# 3_way_omnetics_small.net
KiCad netlist of a schematic drawn in EAGLE
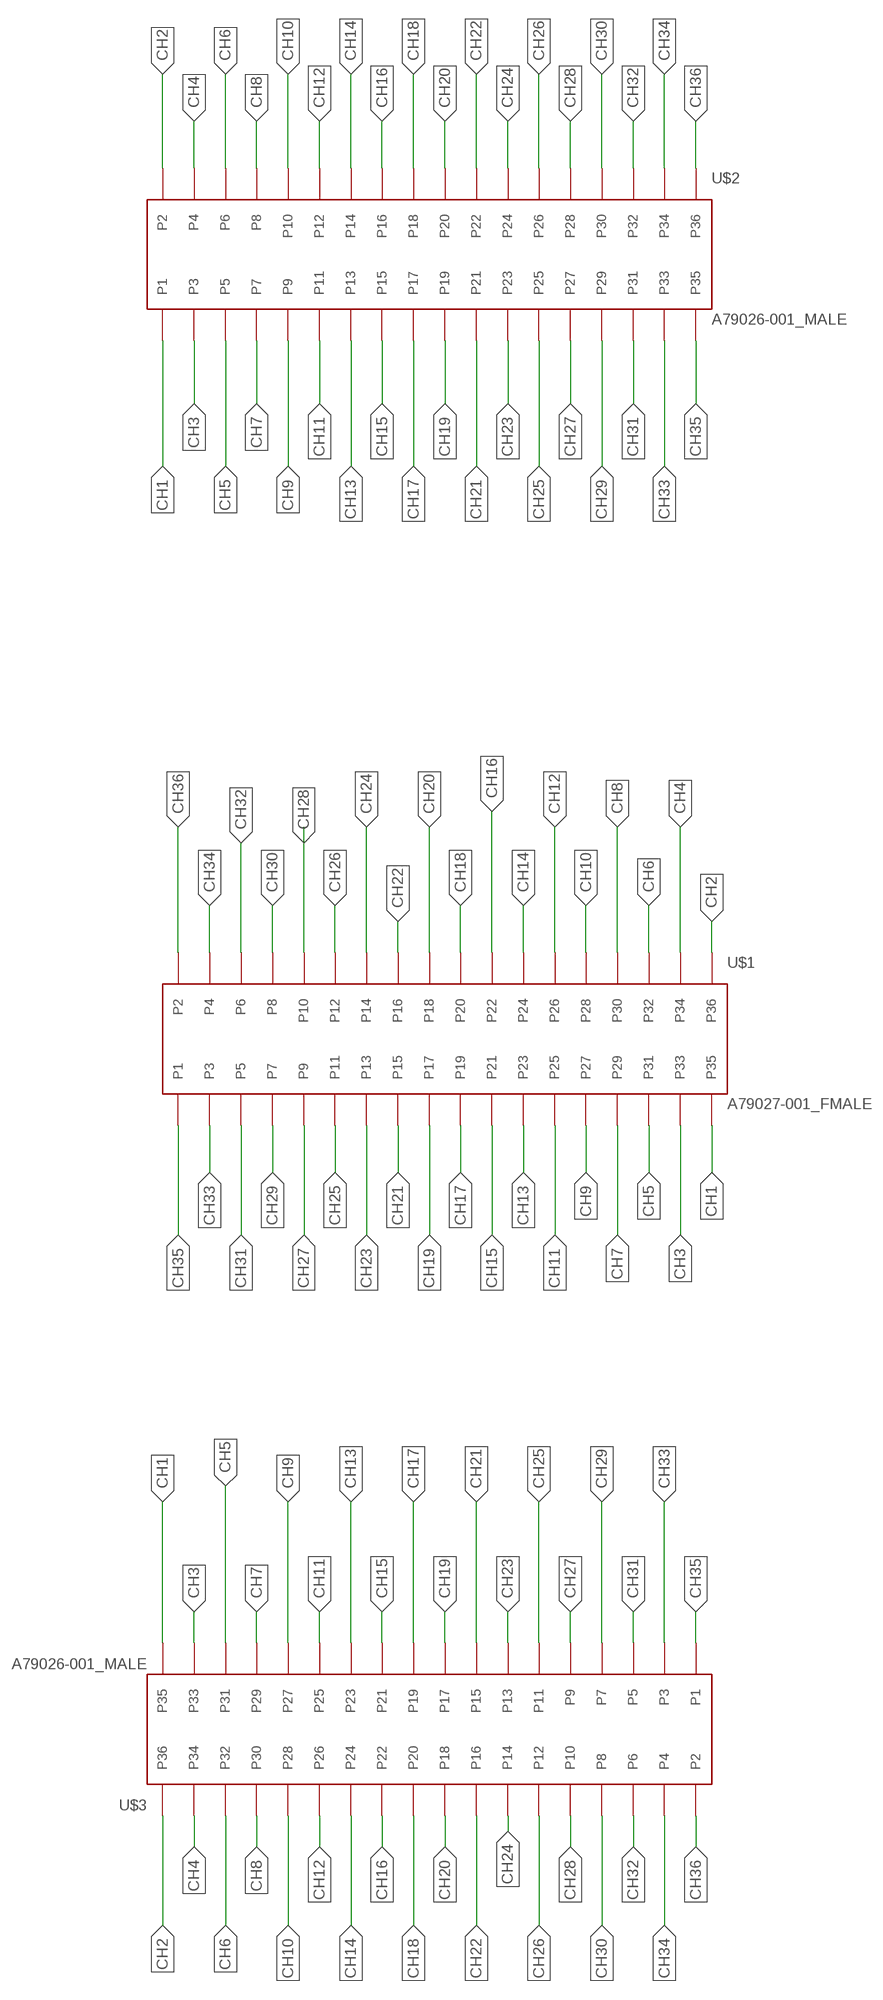
[diagram p0: schematic, sheet 1]

(export (version "E")
  (design (tool "Eeschema 10.0.6"))
  (components
    (comp (ref "U$1")
      (value "A79027-001_FMALE")
      (footprint "eagle-import:A79026-001_MALE")
      (libsource (lib "eagle-import") (part "A79027-001_FMALE"))
    )
    (comp (ref "U$2")
      (value "A79026-001_MALE")
      (footprint "eagle-import:A79026-001_MALE")
      (libsource (lib "eagle-import") (part "A79026-001_MALE"))
    )
    (comp (ref "U$3")
      (value "A79026-001_MALE")
      (footprint "eagle-import:A79026-001_MALE")
      (libsource (lib "eagle-import") (part "A79026-001_MALE"))
    )
  )
  (nets
    (net (code "1") (name "CH1") (class "Default")
      (node (ref "U$1") (pin "P35") (pinfunction "P35_P35") (pintype "bidirectional"))
      (node (ref "U$2") (pin "P1") (pinfunction "P1_P1") (pintype "bidirectional"))
      (node (ref "U$3") (pin "P35") (pinfunction "P35_P35") (pintype "bidirectional"))
    )
    (net (code "2") (name "CH2") (class "Default")
      (node (ref "U$1") (pin "P36") (pinfunction "P36_P36") (pintype "bidirectional"))
      (node (ref "U$2") (pin "P2") (pinfunction "P2_P2") (pintype "bidirectional"))
      (node (ref "U$3") (pin "P36") (pinfunction "P36_P36") (pintype "bidirectional"))
    )
    (net (code "3") (name "CH3") (class "Default")
      (node (ref "U$1") (pin "P33") (pinfunction "P33_P33") (pintype "bidirectional"))
      (node (ref "U$2") (pin "P3") (pinfunction "P3_P3") (pintype "bidirectional"))
      (node (ref "U$3") (pin "P33") (pinfunction "P33_P33") (pintype "bidirectional"))
    )
    (net (code "4") (name "CH4") (class "Default")
      (node (ref "U$1") (pin "P34") (pinfunction "P34_P34") (pintype "bidirectional"))
      (node (ref "U$2") (pin "P4") (pinfunction "P4_P4") (pintype "bidirectional"))
      (node (ref "U$3") (pin "P34") (pinfunction "P34_P34") (pintype "bidirectional"))
    )
    (net (code "5") (name "CH5") (class "Default")
      (node (ref "U$1") (pin "P31") (pinfunction "P31_P31") (pintype "bidirectional"))
      (node (ref "U$2") (pin "P5") (pinfunction "P5_P5") (pintype "bidirectional"))
      (node (ref "U$3") (pin "P31") (pinfunction "P31_P31") (pintype "bidirectional"))
    )
    (net (code "6") (name "CH6") (class "Default")
      (node (ref "U$1") (pin "P32") (pinfunction "P32_P32") (pintype "bidirectional"))
      (node (ref "U$2") (pin "P6") (pinfunction "P6_P6") (pintype "bidirectional"))
      (node (ref "U$3") (pin "P32") (pinfunction "P32_P32") (pintype "bidirectional"))
    )
    (net (code "7") (name "CH7") (class "Default")
      (node (ref "U$1") (pin "P29") (pinfunction "P29_P29") (pintype "bidirectional"))
      (node (ref "U$2") (pin "P7") (pinfunction "P7_P7") (pintype "bidirectional"))
      (node (ref "U$3") (pin "P29") (pinfunction "P29_P29") (pintype "bidirectional"))
    )
    (net (code "8") (name "CH8") (class "Default")
      (node (ref "U$1") (pin "P30") (pinfunction "P30_P30") (pintype "bidirectional"))
      (node (ref "U$2") (pin "P8") (pinfunction "P8_P8") (pintype "bidirectional"))
      (node (ref "U$3") (pin "P30") (pinfunction "P30_P30") (pintype "bidirectional"))
    )
    (net (code "9") (name "CH9") (class "Default")
      (node (ref "U$1") (pin "P27") (pinfunction "P27_P27") (pintype "bidirectional"))
      (node (ref "U$2") (pin "P9") (pinfunction "P9_P9") (pintype "bidirectional"))
      (node (ref "U$3") (pin "P27") (pinfunction "P27_P27") (pintype "bidirectional"))
    )
    (net (code "10") (name "CH10") (class "Default")
      (node (ref "U$1") (pin "P28") (pinfunction "P28_P28") (pintype "bidirectional"))
      (node (ref "U$2") (pin "P10") (pinfunction "P10_P10") (pintype "bidirectional"))
      (node (ref "U$3") (pin "P28") (pinfunction "P28_P28") (pintype "bidirectional"))
    )
    (net (code "11") (name "CH11") (class "Default")
      (node (ref "U$1") (pin "P25") (pinfunction "P25_P25") (pintype "bidirectional"))
      (node (ref "U$2") (pin "P11") (pinfunction "P11_P11") (pintype "bidirectional"))
      (node (ref "U$3") (pin "P25") (pinfunction "P25_P25") (pintype "bidirectional"))
    )
    (net (code "12") (name "CH12") (class "Default")
      (node (ref "U$1") (pin "P26") (pinfunction "P26_P26") (pintype "bidirectional"))
      (node (ref "U$2") (pin "P12") (pinfunction "P12_P12") (pintype "bidirectional"))
      (node (ref "U$3") (pin "P26") (pinfunction "P26_P26") (pintype "bidirectional"))
    )
    (net (code "13") (name "CH13") (class "Default")
      (node (ref "U$1") (pin "P23") (pinfunction "P23_P23") (pintype "bidirectional"))
      (node (ref "U$2") (pin "P13") (pinfunction "P13_P13") (pintype "bidirectional"))
      (node (ref "U$3") (pin "P23") (pinfunction "P23_P23") (pintype "bidirectional"))
    )
    (net (code "14") (name "CH14") (class "Default")
      (node (ref "U$1") (pin "P24") (pinfunction "P24_P24") (pintype "bidirectional"))
      (node (ref "U$2") (pin "P14") (pinfunction "P14_P14") (pintype "bidirectional"))
      (node (ref "U$3") (pin "P24") (pinfunction "P24_P24") (pintype "bidirectional"))
    )
    (net (code "15") (name "CH15") (class "Default")
      (node (ref "U$1") (pin "P21") (pinfunction "P21_P21") (pintype "bidirectional"))
      (node (ref "U$2") (pin "P15") (pinfunction "P15_P15") (pintype "bidirectional"))
      (node (ref "U$3") (pin "P21") (pinfunction "P21_P21") (pintype "bidirectional"))
    )
    (net (code "16") (name "CH16") (class "Default")
      (node (ref "U$1") (pin "P22") (pinfunction "P22_P22") (pintype "bidirectional"))
      (node (ref "U$2") (pin "P16") (pinfunction "P16_P16") (pintype "bidirectional"))
      (node (ref "U$3") (pin "P22") (pinfunction "P22_P22") (pintype "bidirectional"))
    )
    (net (code "17") (name "CH17") (class "Default")
      (node (ref "U$1") (pin "P19") (pinfunction "P19_P19") (pintype "bidirectional"))
      (node (ref "U$2") (pin "P17") (pinfunction "P17_P17") (pintype "bidirectional"))
      (node (ref "U$3") (pin "P19") (pinfunction "P19_P19") (pintype "bidirectional"))
    )
    (net (code "18") (name "CH18") (class "Default")
      (node (ref "U$1") (pin "P20") (pinfunction "P20_P20") (pintype "bidirectional"))
      (node (ref "U$2") (pin "P18") (pinfunction "P18_P18") (pintype "bidirectional"))
      (node (ref "U$3") (pin "P20") (pinfunction "P20_P20") (pintype "bidirectional"))
    )
    (net (code "19") (name "CH19") (class "Default")
      (node (ref "U$1") (pin "P17") (pinfunction "P17_P17") (pintype "bidirectional"))
      (node (ref "U$2") (pin "P19") (pinfunction "P19_P19") (pintype "bidirectional"))
      (node (ref "U$3") (pin "P17") (pinfunction "P17_P17") (pintype "bidirectional"))
    )
    (net (code "20") (name "CH20") (class "Default")
      (node (ref "U$1") (pin "P18") (pinfunction "P18_P18") (pintype "bidirectional"))
      (node (ref "U$2") (pin "P20") (pinfunction "P20_P20") (pintype "bidirectional"))
      (node (ref "U$3") (pin "P18") (pinfunction "P18_P18") (pintype "bidirectional"))
    )
    (net (code "21") (name "CH21") (class "Default")
      (node (ref "U$1") (pin "P15") (pinfunction "P15_P15") (pintype "bidirectional"))
      (node (ref "U$2") (pin "P21") (pinfunction "P21_P21") (pintype "bidirectional"))
      (node (ref "U$3") (pin "P15") (pinfunction "P15_P15") (pintype "bidirectional"))
    )
    (net (code "22") (name "CH22") (class "Default")
      (node (ref "U$1") (pin "P16") (pinfunction "P16_P16") (pintype "bidirectional"))
      (node (ref "U$2") (pin "P22") (pinfunction "P22_P22") (pintype "bidirectional"))
      (node (ref "U$3") (pin "P16") (pinfunction "P16_P16") (pintype "bidirectional"))
    )
    (net (code "23") (name "CH23") (class "Default")
      (node (ref "U$1") (pin "P13") (pinfunction "P13_P13") (pintype "bidirectional"))
      (node (ref "U$2") (pin "P23") (pinfunction "P23_P23") (pintype "bidirectional"))
      (node (ref "U$3") (pin "P13") (pinfunction "P13_P13") (pintype "bidirectional"))
    )
    (net (code "24") (name "CH24") (class "Default")
      (node (ref "U$1") (pin "P14") (pinfunction "P14_P14") (pintype "bidirectional"))
      (node (ref "U$2") (pin "P24") (pinfunction "P24_P24") (pintype "bidirectional"))
      (node (ref "U$3") (pin "P14") (pinfunction "P14_P14") (pintype "bidirectional"))
    )
    (net (code "25") (name "CH25") (class "Default")
      (node (ref "U$1") (pin "P11") (pinfunction "P11_P11") (pintype "bidirectional"))
      (node (ref "U$2") (pin "P25") (pinfunction "P25_P25") (pintype "bidirectional"))
      (node (ref "U$3") (pin "P11") (pinfunction "P11_P11") (pintype "bidirectional"))
    )
    (net (code "26") (name "CH26") (class "Default")
      (node (ref "U$1") (pin "P12") (pinfunction "P12_P12") (pintype "bidirectional"))
      (node (ref "U$2") (pin "P26") (pinfunction "P26_P26") (pintype "bidirectional"))
      (node (ref "U$3") (pin "P12") (pinfunction "P12_P12") (pintype "bidirectional"))
    )
    (net (code "27") (name "CH27") (class "Default")
      (node (ref "U$1") (pin "P9") (pinfunction "P9_P9") (pintype "bidirectional"))
      (node (ref "U$2") (pin "P27") (pinfunction "P27_P27") (pintype "bidirectional"))
      (node (ref "U$3") (pin "P9") (pinfunction "P9_P9") (pintype "bidirectional"))
    )
    (net (code "28") (name "CH28") (class "Default")
      (node (ref "U$1") (pin "P10") (pinfunction "P10_P10") (pintype "bidirectional"))
      (node (ref "U$2") (pin "P28") (pinfunction "P28_P28") (pintype "bidirectional"))
      (node (ref "U$3") (pin "P10") (pinfunction "P10_P10") (pintype "bidirectional"))
    )
    (net (code "29") (name "CH29") (class "Default")
      (node (ref "U$1") (pin "P7") (pinfunction "P7_P7") (pintype "bidirectional"))
      (node (ref "U$2") (pin "P29") (pinfunction "P29_P29") (pintype "bidirectional"))
      (node (ref "U$3") (pin "P7") (pinfunction "P7_P7") (pintype "bidirectional"))
    )
    (net (code "30") (name "CH30") (class "Default")
      (node (ref "U$1") (pin "P8") (pinfunction "P8_P8") (pintype "bidirectional"))
      (node (ref "U$2") (pin "P30") (pinfunction "P30_P30") (pintype "bidirectional"))
      (node (ref "U$3") (pin "P8") (pinfunction "P8_P8") (pintype "bidirectional"))
    )
    (net (code "31") (name "CH31") (class "Default")
      (node (ref "U$1") (pin "P5") (pinfunction "P5_P5") (pintype "bidirectional"))
      (node (ref "U$2") (pin "P31") (pinfunction "P31_P31") (pintype "bidirectional"))
      (node (ref "U$3") (pin "P5") (pinfunction "P5_P5") (pintype "bidirectional"))
    )
    (net (code "32") (name "CH32") (class "Default")
      (node (ref "U$1") (pin "P6") (pinfunction "P6_P6") (pintype "bidirectional"))
      (node (ref "U$2") (pin "P32") (pinfunction "P32_P32") (pintype "bidirectional"))
      (node (ref "U$3") (pin "P6") (pinfunction "P6_P6") (pintype "bidirectional"))
    )
    (net (code "33") (name "CH33") (class "Default")
      (node (ref "U$1") (pin "P3") (pinfunction "P3_P3") (pintype "bidirectional"))
      (node (ref "U$2") (pin "P33") (pinfunction "P33_P33") (pintype "bidirectional"))
      (node (ref "U$3") (pin "P3") (pinfunction "P3_P3") (pintype "bidirectional"))
    )
    (net (code "34") (name "CH34") (class "Default")
      (node (ref "U$1") (pin "P4") (pinfunction "P4_P4") (pintype "bidirectional"))
      (node (ref "U$2") (pin "P34") (pinfunction "P34_P34") (pintype "bidirectional"))
      (node (ref "U$3") (pin "P4") (pinfunction "P4_P4") (pintype "bidirectional"))
    )
    (net (code "35") (name "CH35") (class "Default")
      (node (ref "U$1") (pin "P1") (pinfunction "P1_P1") (pintype "bidirectional"))
      (node (ref "U$2") (pin "P35") (pinfunction "P35_P35") (pintype "bidirectional"))
      (node (ref "U$3") (pin "P1") (pinfunction "P1_P1") (pintype "bidirectional"))
    )
    (net (code "36") (name "CH36") (class "Default")
      (node (ref "U$1") (pin "P2") (pinfunction "P2_P2") (pintype "bidirectional"))
      (node (ref "U$2") (pin "P36") (pinfunction "P36_P36") (pintype "bidirectional"))
      (node (ref "U$3") (pin "P2") (pinfunction "P2_P2") (pintype "bidirectional"))
    )
  )
)
